# Counter.net
KiCad netlist of a schematic drawn in EAGLE
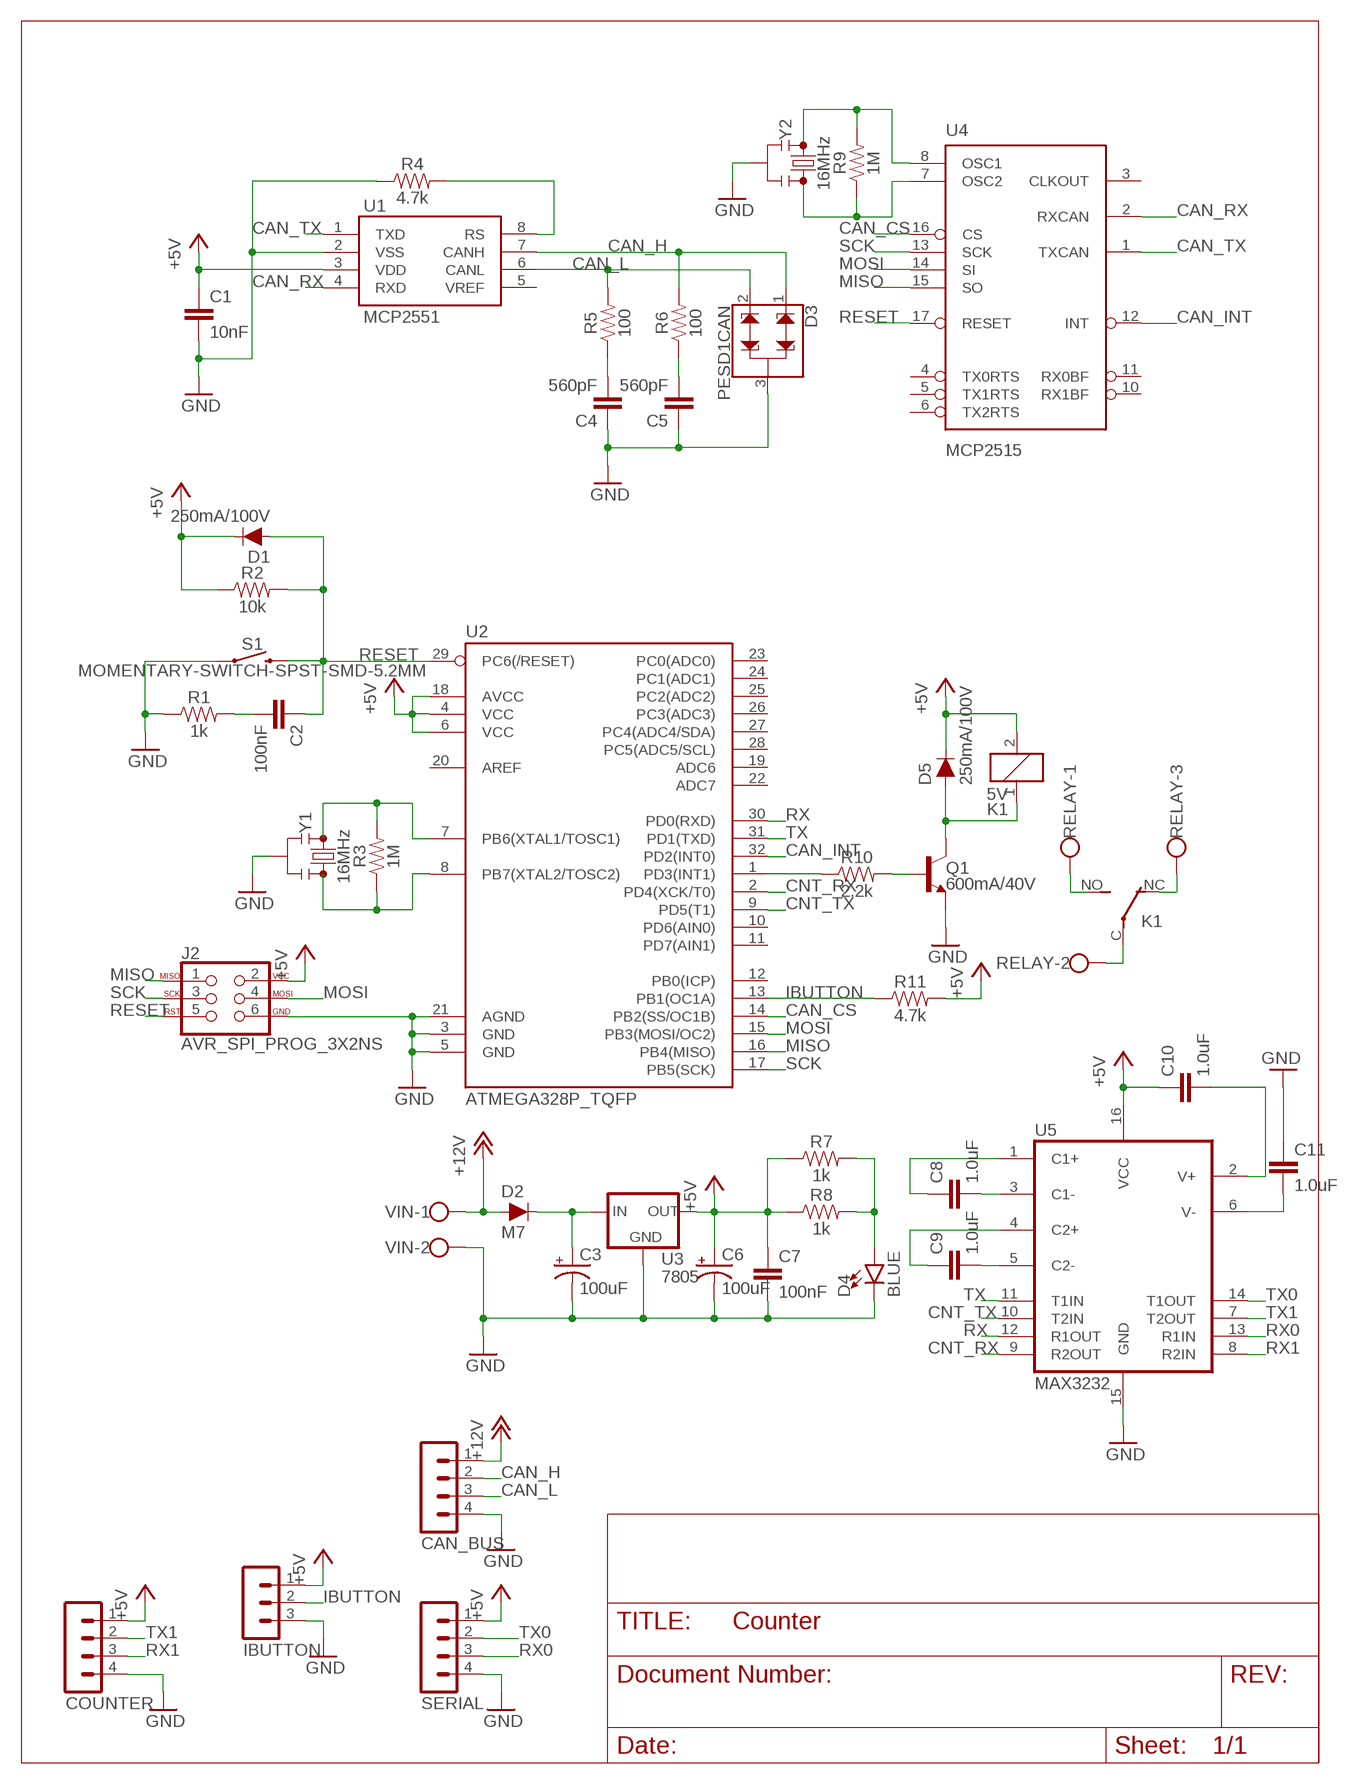
[diagram p0: schematic, sheet 1]

(export (version "E")
  (design (tool "Eeschema 10.0.6"))
  (components
    (comp (ref "C1")
      (value "10nF")
      (footprint "eagle-import:0603")
      (libsource (lib "eagle-import") (part "47NF-0603-25V-5%"))
    )
    (comp (ref "C2")
      (value "100nF")
      (footprint "eagle-import:0603")
      (libsource (lib "eagle-import") (part "47NF-0603-25V-5%"))
    )
    (comp (ref "C3")
      (value "100uF")
      (footprint "eagle-import:PANASONIC_D")
      (libsource (lib "eagle-import") (part "47UF-POLAR-PANASONIC_D-35V-20%"))
    )
    (comp (ref "C4")
      (value "560pF")
      (footprint "eagle-import:0603")
      (libsource (lib "eagle-import") (part "560PF-0603-50V-5%"))
    )
    (comp (ref "C5")
      (value "560pF")
      (footprint "eagle-import:0603")
      (libsource (lib "eagle-import") (part "560PF-0603-50V-5%"))
    )
    (comp (ref "C6")
      (value "100uF")
      (footprint "eagle-import:PANASONIC_D")
      (libsource (lib "eagle-import") (part "47UF-POLAR-PANASONIC_D-35V-20%"))
    )
    (comp (ref "C7")
      (value "100nF")
      (footprint "eagle-import:0603")
      (libsource (lib "eagle-import") (part "47NF-0603-25V-5%"))
    )
    (comp (ref "C8")
      (value "1.0uF")
      (footprint "eagle-import:0603")
      (libsource (lib "eagle-import") (part "1.0UF-0603-16V-10%"))
    )
    (comp (ref "C9")
      (value "1.0uF")
      (footprint "eagle-import:0603")
      (libsource (lib "eagle-import") (part "1.0UF-0603-16V-10%"))
    )
    (comp (ref "C10")
      (value "1.0uF")
      (footprint "eagle-import:0603")
      (libsource (lib "eagle-import") (part "1.0UF-0603-16V-10%"))
    )
    (comp (ref "C11")
      (value "1.0uF")
      (footprint "eagle-import:0603")
      (libsource (lib "eagle-import") (part "1.0UF-0603-16V-10%"))
    )
    (comp (ref "CAN_BUS")
      (value "MA04-1")
      (footprint "eagle-import:MA04-1")
      (libsource (lib "eagle-import") (part "MA04-1"))
    )
    (comp (ref "COUNTER")
      (value "MA04-1")
      (footprint "eagle-import:MA04-1")
      (libsource (lib "eagle-import") (part "MA04-1"))
    )
    (comp (ref "D1")
      (value "250mA/100V")
      (footprint "eagle-import:SOD-323")
      (libsource (lib "eagle-import") (part "DIODE-BAS16J"))
    )
    (comp (ref "D2")
      (value "M7")
      (footprint "eagle-import:SOD-323")
      (libsource (lib "eagle-import") (part "DIODE-BAS16J"))
    )
    (comp (ref "D3")
      (value "PESD1CAN")
      (footprint "eagle-import:SOT23-3")
      (libsource (lib "eagle-import") (part "PESD1CAN"))
    )
    (comp (ref "D4")
      (value "BLUE")
      (footprint "eagle-import:LED-0603")
      (libsource (lib "eagle-import") (part "LED-BLUE0603"))
    )
    (comp (ref "D5")
      (value "250mA/100V")
      (footprint "eagle-import:SOD-323")
      (libsource (lib "eagle-import") (part "DIODE-BAS16J"))
    )
    (comp (ref "IBUTTON")
      (value "MA03-1")
      (footprint "eagle-import:MA03-1")
      (libsource (lib "eagle-import") (part "MA03-1"))
    )
    (comp (ref "J2")
      (value "AVR_SPI_PROG_3X2NS")
      (footprint "eagle-import:2X3-NS")
      (libsource (lib "eagle-import") (part "AVR_SPI_PROG_3X2NS"))
    )
    (comp (ref "K1")
      (value "5V")
      (footprint "eagle-import:CQ1")
      (libsource (lib "eagle-import") (part "CQ1-12V"))
    )
    (comp (ref "Q1")
      (value "600mA/40V")
      (footprint "eagle-import:SOT23-3")
      (libsource (lib "eagle-import") (part "TRANS_NPN-MMBT2222AL"))
    )
    (comp (ref "R1")
      (value "1k")
      (footprint "eagle-import:0603")
      (libsource (lib "eagle-import") (part "1KOHM-0603-1/10W-1%"))
    )
    (comp (ref "R2")
      (value "10k")
      (footprint "eagle-import:0603")
      (libsource (lib "eagle-import") (part "10KOHM-0603-1/10W-1%"))
    )
    (comp (ref "R3")
      (value "1M")
      (footprint "eagle-import:0603")
      (libsource (lib "eagle-import") (part "1MOHM-0603-1/4W-5%"))
    )
    (comp (ref "R4")
      (value "4.7k")
      (footprint "eagle-import:0603")
      (libsource (lib "eagle-import") (part "4.7KOHM-0603-1/10W-1%"))
    )
    (comp (ref "R5")
      (value "100")
      (footprint "eagle-import:0603")
      (libsource (lib "eagle-import") (part "100OHM-0603-1/10W-1%"))
    )
    (comp (ref "R6")
      (value "100")
      (footprint "eagle-import:0603")
      (libsource (lib "eagle-import") (part "100OHM-0603-1/10W-1%"))
    )
    (comp (ref "R7")
      (value "1k")
      (footprint "eagle-import:0603")
      (libsource (lib "eagle-import") (part "1KOHM-0603-1/10W-1%"))
    )
    (comp (ref "R8")
      (value "1k")
      (footprint "eagle-import:0603")
      (libsource (lib "eagle-import") (part "1KOHM-0603-1/10W-1%"))
    )
    (comp (ref "R9")
      (value "1M")
      (footprint "eagle-import:0603")
      (libsource (lib "eagle-import") (part "1MOHM-0603-1/4W-5%"))
    )
    (comp (ref "R10")
      (value "2.2k")
      (footprint "eagle-import:0603")
      (libsource (lib "eagle-import") (part "2.2KOHM-0603-1/10W-1%"))
    )
    (comp (ref "R11")
      (value "4.7k")
      (footprint "eagle-import:0603")
      (libsource (lib "eagle-import") (part "4.7KOHM-0603-1/10W-1%"))
    )
    (comp (ref "RELAY")
      (value "W237-103")
      (footprint "eagle-import:W237-103")
      (fields (field (name "MPN") "237-103"))
      (libsource (lib "eagle-import") (part "W237-103"))
    )
    (comp (ref "S1")
      (value "MOMENTARY-SWITCH-SPST-SMD-5.2MM")
      (footprint "eagle-import:TACTILE_SWITCH_SMD_5.2MM")
      (libsource (lib "eagle-import") (part "MOMENTARY-SWITCH-SPST-SMD-5.2MM"))
    )
    (comp (ref "SERIAL")
      (value "MA04-1")
      (footprint "eagle-import:MA04-1")
      (libsource (lib "eagle-import") (part "MA04-1"))
    )
    (comp (ref "U1")
      (value "MCP2551")
      (footprint "eagle-import:SO08")
      (libsource (lib "eagle-import") (part "MCP2551"))
    )
    (comp (ref "U2")
      (value "ATMEGA328P_TQFP")
      (footprint "eagle-import:TQFP32-08")
      (libsource (lib "eagle-import") (part "ATMEGA328P_TQFP"))
    )
    (comp (ref "U3")
      (value "7805")
      (footprint "eagle-import:TO-252")
      (libsource (lib "eagle-import") (part "V_REG_78XX7812"))
    )
    (comp (ref "U4")
      (value "MCP2515")
      (footprint "eagle-import:SO18W")
      (libsource (lib "eagle-import") (part "MCP2515(MCP2510)SO"))
    )
    (comp (ref "U5")
      (value "MAX3232")
      (footprint "eagle-import:SO16")
      (libsource (lib "eagle-import") (part "MAX2323SOIC16"))
    )
    (comp (ref "VIN")
      (value "W237-102")
      (footprint "eagle-import:W237-102")
      (fields (field (name "MPN") "237-102"))
      (libsource (lib "eagle-import") (part "W237-102"))
    )
    (comp (ref "Y1")
      (value "16MHz")
      (footprint "eagle-import:RESONATOR-SMD-3.2X1.3")
      (libsource (lib "eagle-import") (part "RESONATOR-16MHZSMD_3.2X1.3"))
    )
    (comp (ref "Y2")
      (value "16MHz")
      (footprint "eagle-import:RESONATOR-SMD-3.2X1.3")
      (libsource (lib "eagle-import") (part "RESONATOR-16MHZSMD_3.2X1.3"))
    )
  )
  (nets
    (net (code "1") (name "+5V") (class "Default")
      (node (ref "C1") (pin "1") (pinfunction "1_1") (pintype "passive"))
      (node (ref "C10") (pin "1") (pinfunction "1_1") (pintype "passive"))
      (node (ref "C6") (pin "+") (pinfunction "+_+") (pintype "passive"))
      (node (ref "C7") (pin "1") (pinfunction "1_1") (pintype "passive"))
      (node (ref "COUNTER") (pin "1") (pinfunction "1_1") (pintype "passive"))
      (node (ref "D1") (pin "C") (pinfunction "C_C") (pintype "passive"))
      (node (ref "D5") (pin "C") (pinfunction "C_C") (pintype "passive"))
      (node (ref "IBUTTON") (pin "1") (pinfunction "1_1") (pintype "passive"))
      (node (ref "J2") (pin "2") (pinfunction "2_2") (pintype "passive"))
      (node (ref "K1") (pin "2") (pinfunction "2_2") (pintype "passive"))
      (node (ref "R11") (pin "2") (pinfunction "2_2") (pintype "passive"))
      (node (ref "R2") (pin "1") (pinfunction "1_1") (pintype "passive"))
      (node (ref "R7") (pin "1") (pinfunction "1_1") (pintype "passive"))
      (node (ref "R8") (pin "1") (pinfunction "1_1") (pintype "passive"))
      (node (ref "SERIAL") (pin "1") (pinfunction "1_1") (pintype "passive"))
      (node (ref "U1") (pin "3") (pinfunction "VDD_3") (pintype "bidirectional"))
      (node (ref "U2") (pin "18") (pinfunction "AVCC_18") (pintype "bidirectional"))
      (node (ref "U2") (pin "4") (pinfunction "VCC_4") (pintype "bidirectional"))
      (node (ref "U2") (pin "6") (pinfunction "VCC_6") (pintype "bidirectional"))
      (node (ref "U3") (pin "2") (pinfunction "OUT_2") (pintype "passive"))
      (node (ref "U5") (pin "16") (pinfunction "VCC_16") (pintype "bidirectional"))
    )
    (net (code "2") (name "+12V") (class "Default")
      (node (ref "CAN_BUS") (pin "1") (pinfunction "1_1") (pintype "passive"))
      (node (ref "D2") (pin "A") (pinfunction "A_A") (pintype "passive"))
      (node (ref "VIN") (pin "1") (pinfunction "KL_1") (pintype "passive"))
    )
    (net (code "3") (name "/CAN_CS") (class "Default")
      (node (ref "U2") (pin "14") (pinfunction "PB2(SS/OC1B)_14") (pintype "bidirectional"))
      (node (ref "U4") (pin "16") (pinfunction "CS_16") (pintype "input"))
    )
    (net (code "4") (name "/CAN_H") (class "Default")
      (node (ref "CAN_BUS") (pin "2") (pinfunction "2_2") (pintype "passive"))
      (node (ref "D3") (pin "1") (pinfunction "1_1") (pintype "bidirectional"))
      (node (ref "R6") (pin "2") (pinfunction "2_2") (pintype "passive"))
      (node (ref "U1") (pin "7") (pinfunction "CANH_7") (pintype "bidirectional"))
    )
    (net (code "5") (name "/CAN_INT") (class "Default")
      (node (ref "U2") (pin "32") (pinfunction "PD2(INT0)_32") (pintype "bidirectional"))
      (node (ref "U4") (pin "12") (pinfunction "INT_12") (pintype "output"))
    )
    (net (code "6") (name "/CAN_L") (class "Default")
      (node (ref "CAN_BUS") (pin "3") (pinfunction "3_3") (pintype "passive"))
      (node (ref "D3") (pin "2") (pinfunction "2_2") (pintype "bidirectional"))
      (node (ref "R5") (pin "2") (pinfunction "2_2") (pintype "passive"))
      (node (ref "U1") (pin "6") (pinfunction "CANL_6") (pintype "bidirectional"))
    )
    (net (code "7") (name "/CAN_RX") (class "Default")
      (node (ref "U1") (pin "4") (pinfunction "RXD_4") (pintype "bidirectional"))
      (node (ref "U4") (pin "2") (pinfunction "RXCAN_2") (pintype "input"))
    )
    (net (code "8") (name "/CAN_TX") (class "Default")
      (node (ref "U1") (pin "1") (pinfunction "TXD_1") (pintype "bidirectional"))
      (node (ref "U4") (pin "1") (pinfunction "TXCAN_1") (pintype "output"))
    )
    (net (code "9") (name "/CNT_RX") (class "Default")
      (node (ref "U2") (pin "2") (pinfunction "PD4(XCK/T0)_2") (pintype "bidirectional"))
      (node (ref "U5") (pin "9") (pinfunction "R2OUT_9") (pintype "output"))
    )
    (net (code "10") (name "/CNT_TX") (class "Default")
      (node (ref "U2") (pin "9") (pinfunction "PD5(T1)_9") (pintype "bidirectional"))
      (node (ref "U5") (pin "10") (pinfunction "T2IN_10") (pintype "input"))
    )
    (net (code "11") (name "/IBUTTON") (class "Default")
      (node (ref "IBUTTON") (pin "2") (pinfunction "2_2") (pintype "passive"))
      (node (ref "R11") (pin "1") (pinfunction "1_1") (pintype "passive"))
      (node (ref "U2") (pin "13") (pinfunction "PB1(OC1A)_13") (pintype "bidirectional"))
    )
    (net (code "12") (name "/MISO") (class "Default")
      (node (ref "J2") (pin "1") (pinfunction "1_1") (pintype "passive"))
      (node (ref "U2") (pin "16") (pinfunction "PB4(MISO)_16") (pintype "bidirectional"))
      (node (ref "U4") (pin "15") (pinfunction "SO_15") (pintype "output"))
    )
    (net (code "13") (name "/MOSI") (class "Default")
      (node (ref "J2") (pin "4") (pinfunction "4_4") (pintype "passive"))
      (node (ref "U2") (pin "15") (pinfunction "PB3(MOSI/OC2)_15") (pintype "bidirectional"))
      (node (ref "U4") (pin "14") (pinfunction "SI_14") (pintype "input"))
    )
    (net (code "14") (name "/RESET") (class "Default")
      (node (ref "C2") (pin "1") (pinfunction "1_1") (pintype "passive"))
      (node (ref "D1") (pin "A") (pinfunction "A_A") (pintype "passive"))
      (node (ref "J2") (pin "5") (pinfunction "5_5") (pintype "passive"))
      (node (ref "R2") (pin "2") (pinfunction "2_2") (pintype "passive"))
      (node (ref "S1") (pin "3") (pinfunction "2_3") (pintype "passive"))
      (node (ref "U2") (pin "29") (pinfunction "PC6(/RESET)_29") (pintype "bidirectional"))
      (node (ref "U4") (pin "17") (pinfunction "RESET_17") (pintype "input"))
    )
    (net (code "15") (name "/RX") (class "Default")
      (node (ref "U2") (pin "30") (pinfunction "PD0(RXD)_30") (pintype "bidirectional"))
      (node (ref "U5") (pin "12") (pinfunction "R1OUT_12") (pintype "output"))
    )
    (net (code "16") (name "/RX0") (class "Default")
      (node (ref "SERIAL") (pin "3") (pinfunction "3_3") (pintype "passive"))
      (node (ref "U5") (pin "13") (pinfunction "R1IN_13") (pintype "input"))
    )
    (net (code "17") (name "/RX1") (class "Default")
      (node (ref "COUNTER") (pin "3") (pinfunction "3_3") (pintype "passive"))
      (node (ref "U5") (pin "8") (pinfunction "R2IN_8") (pintype "input"))
    )
    (net (code "18") (name "/SCK") (class "Default")
      (node (ref "J2") (pin "3") (pinfunction "3_3") (pintype "passive"))
      (node (ref "U2") (pin "17") (pinfunction "PB5(SCK)_17") (pintype "bidirectional"))
      (node (ref "U4") (pin "13") (pinfunction "SCK_13") (pintype "input"))
    )
    (net (code "19") (name "/TX") (class "Default")
      (node (ref "U2") (pin "31") (pinfunction "PD1(TXD)_31") (pintype "bidirectional"))
      (node (ref "U5") (pin "11") (pinfunction "T1IN_11") (pintype "input"))
    )
    (net (code "20") (name "/TX0") (class "Default")
      (node (ref "SERIAL") (pin "2") (pinfunction "2_2") (pintype "passive"))
      (node (ref "U5") (pin "14") (pinfunction "T1OUT_14") (pintype "output"))
    )
    (net (code "21") (name "/TX1") (class "Default")
      (node (ref "COUNTER") (pin "2") (pinfunction "2_2") (pintype "passive"))
      (node (ref "U5") (pin "7") (pinfunction "T2OUT_7") (pintype "output"))
    )
    (net (code "22") (name "GND") (class "Default")
      (node (ref "C1") (pin "2") (pinfunction "2_2") (pintype "passive"))
      (node (ref "C11") (pin "1") (pinfunction "1_1") (pintype "passive"))
      (node (ref "C3") (pin "-") (pinfunction "-_-") (pintype "passive"))
      (node (ref "C4") (pin "1") (pinfunction "1_1") (pintype "passive"))
      (node (ref "C5") (pin "1") (pinfunction "1_1") (pintype "passive"))
      (node (ref "C6") (pin "-") (pinfunction "-_-") (pintype "passive"))
      (node (ref "C7") (pin "2") (pinfunction "2_2") (pintype "passive"))
      (node (ref "CAN_BUS") (pin "4") (pinfunction "4_4") (pintype "passive"))
      (node (ref "COUNTER") (pin "4") (pinfunction "4_4") (pintype "passive"))
      (node (ref "D3") (pin "3") (pinfunction "3_3") (pintype "bidirectional"))
      (node (ref "D4") (pin "C") (pinfunction "C_C") (pintype "passive"))
      (node (ref "IBUTTON") (pin "3") (pinfunction "3_3") (pintype "passive"))
      (node (ref "J2") (pin "6") (pinfunction "6_6") (pintype "passive"))
      (node (ref "Q1") (pin "2") (pinfunction "E_2") (pintype "passive"))
      (node (ref "R1") (pin "1") (pinfunction "1_1") (pintype "passive"))
      (node (ref "R4") (pin "1") (pinfunction "1_1") (pintype "passive"))
      (node (ref "S1") (pin "1") (pinfunction "1_1") (pintype "passive"))
      (node (ref "SERIAL") (pin "4") (pinfunction "4_4") (pintype "passive"))
      (node (ref "U1") (pin "2") (pinfunction "VSS_2") (pintype "bidirectional"))
      (node (ref "U2") (pin "21") (pinfunction "AGND_21") (pintype "bidirectional"))
      (node (ref "U2") (pin "3") (pinfunction "GND_3") (pintype "bidirectional"))
      (node (ref "U2") (pin "5") (pinfunction "GND_5") (pintype "bidirectional"))
      (node (ref "U3") (pin "3") (pinfunction "GND_3") (pintype "input"))
      (node (ref "U5") (pin "15") (pinfunction "GND_15") (pintype "bidirectional"))
      (node (ref "VIN") (pin "2") (pinfunction "KL_2") (pintype "passive"))
      (node (ref "Y1") (pin "2") (pinfunction "2_2") (pintype "passive"))
      (node (ref "Y2") (pin "2") (pinfunction "2_2") (pintype "passive"))
    )
    (net (code "23") (name "Net-(C2-Pad2)") (class "Default")
      (node (ref "C2") (pin "2") (pinfunction "2_2") (pintype "passive"))
      (node (ref "R1") (pin "2") (pinfunction "2_2") (pintype "passive"))
    )
    (net (code "24") (name "Net-(C4-Pad2)") (class "Default")
      (node (ref "C4") (pin "2") (pinfunction "2_2") (pintype "passive"))
      (node (ref "R5") (pin "1") (pinfunction "1_1") (pintype "passive"))
    )
    (net (code "25") (name "Net-(C5-Pad2)") (class "Default")
      (node (ref "C5") (pin "2") (pinfunction "2_2") (pintype "passive"))
      (node (ref "R6") (pin "1") (pinfunction "1_1") (pintype "passive"))
    )
    (net (code "26") (name "Net-(D4-PadA)") (class "Default")
      (node (ref "D4") (pin "A") (pinfunction "A_A") (pintype "passive"))
      (node (ref "R7") (pin "2") (pinfunction "2_2") (pintype "passive"))
      (node (ref "R8") (pin "2") (pinfunction "2_2") (pintype "passive"))
    )
    (net (code "27") (name "Net-(K1B-O)") (class "Default")
      (node (ref "K1") (pin "NC") (pinfunction "O_NC") (pintype "passive"))
      (node (ref "RELAY") (pin "3") (pinfunction "KL_3") (pintype "passive"))
    )
    (net (code "28") (name "Net-(K1B-P)") (class "Default")
      (node (ref "K1") (pin "C") (pinfunction "P_C") (pintype "passive"))
      (node (ref "RELAY") (pin "2") (pinfunction "KL_2") (pintype "passive"))
    )
    (net (code "29") (name "Net-(K1B-S)") (class "Default")
      (node (ref "K1") (pin "NO") (pinfunction "S_NO") (pintype "passive"))
      (node (ref "RELAY") (pin "1") (pinfunction "KL_1") (pintype "passive"))
    )
    (net (code "30") (name "Net-(Q1-B)") (class "Default")
      (node (ref "Q1") (pin "1") (pinfunction "B_1") (pintype "passive"))
      (node (ref "R10") (pin "2") (pinfunction "2_2") (pintype "passive"))
    )
    (net (code "31") (name "Net-(Q1-C)") (class "Default")
      (node (ref "D5") (pin "A") (pinfunction "A_A") (pintype "passive"))
      (node (ref "K1") (pin "1") (pinfunction "1_1") (pintype "passive"))
      (node (ref "Q1") (pin "3") (pinfunction "C_3") (pintype "passive"))
    )
    (net (code "32") (name "Net-(U1-RS)") (class "Default")
      (node (ref "R4") (pin "2") (pinfunction "2_2") (pintype "passive"))
      (node (ref "U1") (pin "8") (pinfunction "RS_8") (pintype "bidirectional"))
    )
    (net (code "33") (name "Net-(U2-PB6(XTAL1{slash}TOSC1))") (class "Default")
      (node (ref "R3") (pin "2") (pinfunction "2_2") (pintype "passive"))
      (node (ref "U2") (pin "7") (pinfunction "PB6(XTAL1/TOSC1)_7") (pintype "bidirectional"))
      (node (ref "Y1") (pin "1") (pinfunction "1_1") (pintype "passive"))
    )
    (net (code "34") (name "Net-(U2-PB7(XTAL2{slash}TOSC2))") (class "Default")
      (node (ref "R3") (pin "1") (pinfunction "1_1") (pintype "passive"))
      (node (ref "U2") (pin "8") (pinfunction "PB7(XTAL2/TOSC2)_8") (pintype "bidirectional"))
      (node (ref "Y1") (pin "3") (pinfunction "3_3") (pintype "passive"))
    )
    (net (code "35") (name "Net-(U2-PD3(INT1))") (class "Default")
      (node (ref "R10") (pin "1") (pinfunction "1_1") (pintype "passive"))
      (node (ref "U2") (pin "1") (pinfunction "PD3(INT1)_1") (pintype "bidirectional"))
    )
    (net (code "36") (name "Net-(U3-IN)") (class "Default")
      (node (ref "C3") (pin "+") (pinfunction "+_+") (pintype "passive"))
      (node (ref "D2") (pin "C") (pinfunction "C_C") (pintype "passive"))
      (node (ref "U3") (pin "1") (pinfunction "IN_1") (pintype "input"))
    )
    (net (code "37") (name "Net-(U4A-OSC1)") (class "Default")
      (node (ref "R9") (pin "2") (pinfunction "2_2") (pintype "passive"))
      (node (ref "U4") (pin "8") (pinfunction "OSC1_8") (pintype "input"))
      (node (ref "Y2") (pin "1") (pinfunction "1_1") (pintype "passive"))
    )
    (net (code "38") (name "Net-(U4A-OSC2)") (class "Default")
      (node (ref "R9") (pin "1") (pinfunction "1_1") (pintype "passive"))
      (node (ref "U4") (pin "7") (pinfunction "OSC2_7") (pintype "output"))
      (node (ref "Y2") (pin "3") (pinfunction "3_3") (pintype "passive"))
    )
    (net (code "39") (name "Net-(U5-C1+)") (class "Default")
      (node (ref "C8") (pin "1") (pinfunction "1_1") (pintype "passive"))
      (node (ref "U5") (pin "1") (pinfunction "C1+_1") (pintype "bidirectional"))
    )
    (net (code "40") (name "Net-(U5-C1-)") (class "Default")
      (node (ref "C8") (pin "2") (pinfunction "2_2") (pintype "passive"))
      (node (ref "U5") (pin "3") (pinfunction "C1-_3") (pintype "bidirectional"))
    )
    (net (code "41") (name "Net-(U5-C2+)") (class "Default")
      (node (ref "C9") (pin "1") (pinfunction "1_1") (pintype "passive"))
      (node (ref "U5") (pin "4") (pinfunction "C2+_4") (pintype "bidirectional"))
    )
    (net (code "42") (name "Net-(U5-C2-)") (class "Default")
      (node (ref "C9") (pin "2") (pinfunction "2_2") (pintype "passive"))
      (node (ref "U5") (pin "5") (pinfunction "C2-_5") (pintype "bidirectional"))
    )
    (net (code "43") (name "Net-(U5-V+)") (class "Default")
      (node (ref "C10") (pin "2") (pinfunction "2_2") (pintype "passive"))
      (node (ref "U5") (pin "2") (pinfunction "V+_2") (pintype "bidirectional"))
    )
    (net (code "44") (name "Net-(U5-V-)") (class "Default")
      (node (ref "C11") (pin "2") (pinfunction "2_2") (pintype "passive"))
      (node (ref "U5") (pin "6") (pinfunction "V-_6") (pintype "bidirectional"))
    )
    (net (code "45") (name "unconnected-(U1-VREF-Pad5)") (class "Default")
      (node (ref "U1") (pin "5") (pinfunction "VREF_5") (pintype "bidirectional"))
    )
    (net (code "46") (name "unconnected-(U2-ADC6-Pad19)") (class "Default")
      (node (ref "U2") (pin "19") (pinfunction "ADC6_19") (pintype "bidirectional"))
    )
    (net (code "47") (name "unconnected-(U2-ADC7-Pad22)") (class "Default")
      (node (ref "U2") (pin "22") (pinfunction "ADC7_22") (pintype "bidirectional"))
    )
    (net (code "48") (name "unconnected-(U2-AREF-Pad20)") (class "Default")
      (node (ref "U2") (pin "20") (pinfunction "AREF_20") (pintype "bidirectional"))
    )
    (net (code "49") (name "unconnected-(U2-PB0(ICP)-Pad12)") (class "Default")
      (node (ref "U2") (pin "12") (pinfunction "PB0(ICP)_12") (pintype "bidirectional"))
    )
    (net (code "50") (name "unconnected-(U2-PC0(ADC0)-Pad23)") (class "Default")
      (node (ref "U2") (pin "23") (pinfunction "PC0(ADC0)_23") (pintype "bidirectional"))
    )
    (net (code "51") (name "unconnected-(U2-PC1(ADC1)-Pad24)") (class "Default")
      (node (ref "U2") (pin "24") (pinfunction "PC1(ADC1)_24") (pintype "bidirectional"))
    )
    (net (code "52") (name "unconnected-(U2-PC2(ADC2)-Pad25)") (class "Default")
      (node (ref "U2") (pin "25") (pinfunction "PC2(ADC2)_25") (pintype "bidirectional"))
    )
    (net (code "53") (name "unconnected-(U2-PC3(ADC3)-Pad26)") (class "Default")
      (node (ref "U2") (pin "26") (pinfunction "PC3(ADC3)_26") (pintype "bidirectional"))
    )
    (net (code "54") (name "unconnected-(U2-PC4(ADC4{slash}SDA)-Pad27)") (class "Default")
      (node (ref "U2") (pin "27") (pinfunction "PC4(ADC4/SDA)_27") (pintype "bidirectional"))
    )
    (net (code "55") (name "unconnected-(U2-PC5(ADC5{slash}SCL)-Pad28)") (class "Default")
      (node (ref "U2") (pin "28") (pinfunction "PC5(ADC5/SCL)_28") (pintype "bidirectional"))
    )
    (net (code "56") (name "unconnected-(U2-PD6(AIN0)-Pad10)") (class "Default")
      (node (ref "U2") (pin "10") (pinfunction "PD6(AIN0)_10") (pintype "bidirectional"))
    )
    (net (code "57") (name "unconnected-(U2-PD7(AIN1)-Pad11)") (class "Default")
      (node (ref "U2") (pin "11") (pinfunction "PD7(AIN1)_11") (pintype "bidirectional"))
    )
    (net (code "58") (name "unconnected-(U4A-CLKOUT-Pad3)") (class "Default")
      (node (ref "U4") (pin "3") (pinfunction "CLKOUT_3") (pintype "output"))
    )
    (net (code "59") (name "unconnected-(U4A-RX0BF-Pad11)") (class "Default")
      (node (ref "U4") (pin "11") (pinfunction "RX0BF_11") (pintype "output"))
    )
    (net (code "60") (name "unconnected-(U4A-RX1BF-Pad10)") (class "Default")
      (node (ref "U4") (pin "10") (pinfunction "RX1BF_10") (pintype "output"))
    )
    (net (code "61") (name "unconnected-(U4A-TX0RTS-Pad4)") (class "Default")
      (node (ref "U4") (pin "4") (pinfunction "TX0RTS_4") (pintype "input"))
    )
    (net (code "62") (name "unconnected-(U4A-TX1RTS-Pad5)") (class "Default")
      (node (ref "U4") (pin "5") (pinfunction "TX1RTS_5") (pintype "input"))
    )
    (net (code "63") (name "unconnected-(U4A-TX2RTS-Pad6)") (class "Default")
      (node (ref "U4") (pin "6") (pinfunction "TX2RTS_6") (pintype "input"))
    )
  )
)
